# GK_Roland_Breakout.net
KiCad netlist of a schematic drawn in EAGLE
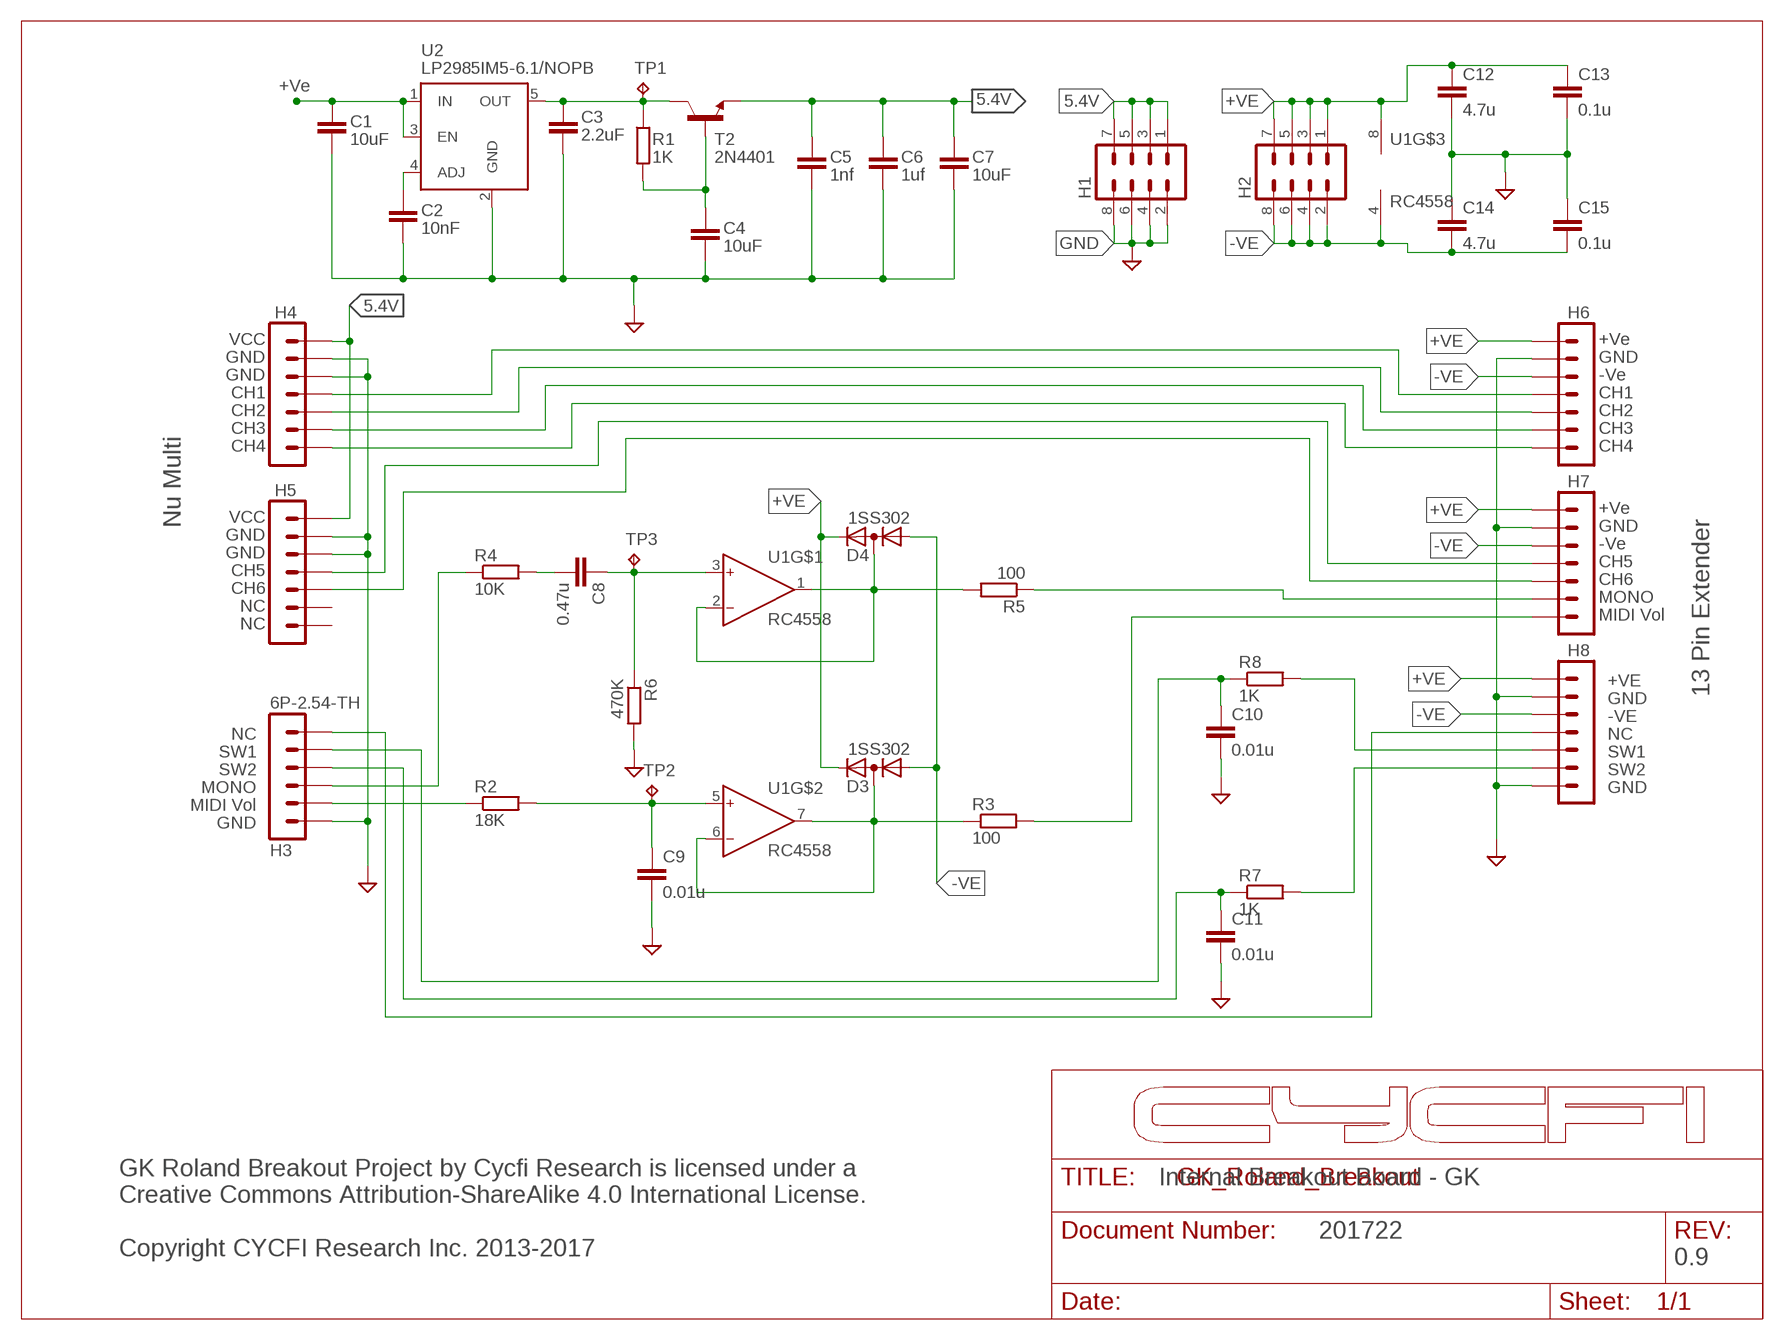
[diagram p0: schematic, sheet 1]

(export (version "E")
  (design (tool "Eeschema 10.0.6"))
  (components
    (comp (ref "C1")
      (value "10uF")
      (footprint "eagle-import:C0805")
      (libsource (lib "eagle-import") (part "C-EUC0805"))
    )
    (comp (ref "C2")
      (value "10nF")
      (footprint "eagle-import:C0805")
      (libsource (lib "eagle-import") (part "C-EUC0805"))
    )
    (comp (ref "C3")
      (value "2.2uF")
      (footprint "eagle-import:C0805")
      (libsource (lib "eagle-import") (part "C-EUC0805"))
    )
    (comp (ref "C4")
      (value "10uF")
      (footprint "eagle-import:C0805")
      (libsource (lib "eagle-import") (part "C-EUC0805"))
    )
    (comp (ref "C5")
      (value "1nf")
      (footprint "eagle-import:C0603")
      (libsource (lib "eagle-import") (part "C-EUC0603"))
    )
    (comp (ref "C6")
      (value "1uf")
      (footprint "eagle-import:C0603")
      (libsource (lib "eagle-import") (part "C-EUC0603"))
    )
    (comp (ref "C7")
      (value "10uF")
      (footprint "eagle-import:C0805")
      (libsource (lib "eagle-import") (part "C-EUC0805"))
    )
    (comp (ref "C8")
      (value "0.47u")
      (footprint "eagle-import:C0805")
      (libsource (lib "eagle-import") (part "C-EUC0805"))
    )
    (comp (ref "C9")
      (value "0.01u")
      (footprint "eagle-import:C0805")
      (libsource (lib "eagle-import") (part "C-EUC0805"))
    )
    (comp (ref "C10")
      (value "0.01u")
      (footprint "eagle-import:C0805")
      (libsource (lib "eagle-import") (part "C-EUC0805"))
    )
    (comp (ref "C11")
      (value "0.01u")
      (footprint "eagle-import:C0805")
      (libsource (lib "eagle-import") (part "C-EUC0805"))
    )
    (comp (ref "C12")
      (value "4.7u")
      (footprint "eagle-import:C0805")
      (libsource (lib "eagle-import") (part "C-EUC0805"))
    )
    (comp (ref "C13")
      (value "0.1u")
      (footprint "eagle-import:C0805")
      (libsource (lib "eagle-import") (part "C-EUC0805"))
    )
    (comp (ref "C14")
      (value "4.7u")
      (footprint "eagle-import:C0805")
      (libsource (lib "eagle-import") (part "C-EUC0805"))
    )
    (comp (ref "C15")
      (value "0.1u")
      (footprint "eagle-import:C0805")
      (libsource (lib "eagle-import") (part "C-EUC0805"))
    )
    (comp (ref "D3")
      (value "1SS302")
      (footprint "eagle-import:SC70-3")
      (libsource (lib "eagle-import") (part "1SS302"))
    )
    (comp (ref "D4")
      (value "1SS302")
      (footprint "eagle-import:SC70-3")
      (libsource (lib "eagle-import") (part "1SS302"))
    )
    (comp (ref "H1")
      (value "MA04-2")
      (footprint "eagle-import:MA04-2")
      (libsource (lib "eagle-import") (part "MA04-2"))
    )
    (comp (ref "H2")
      (value "MA04-2")
      (footprint "eagle-import:MA04-2")
      (libsource (lib "eagle-import") (part "MA04-2"))
    )
    (comp (ref "H3")
      (value "6P-2.54-TH")
      (footprint "eagle-import:6P-2.54-TH")
      (libsource (lib "eagle-import") (part "6P-2.54-TH"))
    )
    (comp (ref "H4")
      (value "7P_ZIF_59453-071110EDHLF")
      (footprint "eagle-import:7P_ZIF_59453-071110EDHLF")
      (libsource (lib "eagle-import") (part "7P_ZIF_59453-071110EDHLF"))
    )
    (comp (ref "H5")
      (value "7P_ZIF_59453-071110EDHLF")
      (footprint "eagle-import:7P_ZIF_59453-071110EDHLF")
      (libsource (lib "eagle-import") (part "7P_ZIF_59453-071110EDHLF"))
    )
    (comp (ref "H6")
      (value "7P_ZIF_59453-071110EDHLF")
      (footprint "eagle-import:7P_ZIF_59453-071110EDHLF")
      (libsource (lib "eagle-import") (part "7P_ZIF_59453-071110EDHLF"))
    )
    (comp (ref "H7")
      (value "7P_ZIF_59453-071110EDHLF")
      (footprint "eagle-import:7P_ZIF_59453-071110EDHLF")
      (libsource (lib "eagle-import") (part "7P_ZIF_59453-071110EDHLF"))
    )
    (comp (ref "H8")
      (value "7P_ZIF_59453-071110EDHLF")
      (footprint "eagle-import:7P_ZIF_59453-071110EDHLF")
      (libsource (lib "eagle-import") (part "7P_ZIF_59453-071110EDHLF"))
    )
    (comp (ref "R1")
      (value "1K")
      (footprint "eagle-import:R0402")
      (libsource (lib "eagle-import") (part "R-EU_R0402"))
    )
    (comp (ref "R2")
      (value "18K")
      (footprint "eagle-import:R0402")
      (libsource (lib "eagle-import") (part "R-EU_R0402"))
    )
    (comp (ref "R3")
      (value "100")
      (footprint "eagle-import:R0402")
      (libsource (lib "eagle-import") (part "R-EU_R0402"))
    )
    (comp (ref "R4")
      (value "10K")
      (footprint "eagle-import:R0402")
      (libsource (lib "eagle-import") (part "R-EU_R0402"))
    )
    (comp (ref "R5")
      (value "100")
      (footprint "eagle-import:R0402")
      (libsource (lib "eagle-import") (part "R-EU_R0402"))
    )
    (comp (ref "R6")
      (value "470K")
      (footprint "eagle-import:R0402")
      (libsource (lib "eagle-import") (part "R-EU_R0402"))
    )
    (comp (ref "R7")
      (value "1K")
      (footprint "eagle-import:R0402")
      (libsource (lib "eagle-import") (part "R-EU_R0402"))
    )
    (comp (ref "R8")
      (value "1K")
      (footprint "eagle-import:R0402")
      (libsource (lib "eagle-import") (part "R-EU_R0402"))
    )
    (comp (ref "T2")
      (value "2N4401")
      (footprint "eagle-import:SOT23-3")
      (libsource (lib "eagle-import") (part "TRAN-MMBT2222A"))
    )
    (comp (ref "TP1")
      (value "TPB1,27")
      (footprint "eagle-import:B1,27")
      (libsource (lib "eagle-import") (part "TPB1,27"))
    )
    (comp (ref "TP2")
      (value "TPB1,27")
      (footprint "eagle-import:B1,27")
      (libsource (lib "eagle-import") (part "TPB1,27"))
    )
    (comp (ref "TP3")
      (value "TPB1,27")
      (footprint "eagle-import:B1,27")
      (libsource (lib "eagle-import") (part "TPB1,27"))
    )
    (comp (ref "U1")
      (value "RC4558")
      (footprint "eagle-import:SOIC-8")
      (libsource (lib "eagle-import") (part "RC4558"))
    )
    (comp (ref "U2")
      (value "MIC5205-5V")
      (footprint "eagle-import:SOT23-5")
      (fields (field (name "MF") "ALTERA CORPORATION") (field (name "MPN") "MIC5219BM5 TR"))
      (libsource (lib "eagle-import") (part "MIC5219BM5"))
    )
  )
  (nets
    (net (code "1") (name "+VE") (class "Default")
      (node (ref "C1") (pin "1") (pinfunction "1_1") (pintype "passive"))
      (node (ref "C12") (pin "1") (pinfunction "1_1") (pintype "passive"))
      (node (ref "C13") (pin "1") (pinfunction "1_1") (pintype "passive"))
      (node (ref "D3") (pin "2") (pinfunction "K_2") (pintype "passive"))
      (node (ref "D4") (pin "2") (pinfunction "K_2") (pintype "passive"))
      (node (ref "H2") (pin "1") (pinfunction "1_1") (pintype "passive"))
      (node (ref "H2") (pin "3") (pinfunction "3_3") (pintype "passive"))
      (node (ref "H2") (pin "5") (pinfunction "5_5") (pintype "passive"))
      (node (ref "H2") (pin "7") (pinfunction "7_7") (pintype "passive"))
      (node (ref "H6") (pin "P$1") (pinfunction "1_P$1") (pintype "passive"))
      (node (ref "H7") (pin "P$1") (pinfunction "1_P$1") (pintype "passive"))
      (node (ref "H8") (pin "P$1") (pinfunction "1_P$1") (pintype "passive"))
      (node (ref "U1") (pin "8") (pinfunction "V+_8") (pintype "power_in"))
      (node (ref "U2") (pin "1") (pinfunction "IN_1") (pintype "input"))
      (node (ref "U2") (pin "3") (pinfunction "EN_3") (pintype "input"))
    )
    (net (code "2") (name "-VE") (class "Default")
      (node (ref "C14") (pin "2") (pinfunction "2_2") (pintype "passive"))
      (node (ref "C15") (pin "2") (pinfunction "2_2") (pintype "passive"))
      (node (ref "D3") (pin "1") (pinfunction "A_1") (pintype "passive"))
      (node (ref "D4") (pin "1") (pinfunction "A_1") (pintype "passive"))
      (node (ref "H2") (pin "2") (pinfunction "2_2") (pintype "passive"))
      (node (ref "H2") (pin "4") (pinfunction "4_4") (pintype "passive"))
      (node (ref "H2") (pin "6") (pinfunction "6_6") (pintype "passive"))
      (node (ref "H2") (pin "8") (pinfunction "8_8") (pintype "passive"))
      (node (ref "H6") (pin "P$3") (pinfunction "3_P$3") (pintype "passive"))
      (node (ref "H7") (pin "P$3") (pinfunction "3_P$3") (pintype "passive"))
      (node (ref "H8") (pin "P$3") (pinfunction "3_P$3") (pintype "passive"))
      (node (ref "U1") (pin "4") (pinfunction "V-_4") (pintype "power_in"))
    )
    (net (code "3") (name "5.4V") (class "Default")
      (node (ref "C5") (pin "1") (pinfunction "1_1") (pintype "passive"))
      (node (ref "C6") (pin "1") (pinfunction "1_1") (pintype "passive"))
      (node (ref "C7") (pin "1") (pinfunction "1_1") (pintype "passive"))
      (node (ref "H1") (pin "1") (pinfunction "1_1") (pintype "passive"))
      (node (ref "H1") (pin "3") (pinfunction "3_3") (pintype "passive"))
      (node (ref "H1") (pin "5") (pinfunction "5_5") (pintype "passive"))
      (node (ref "H1") (pin "7") (pinfunction "7_7") (pintype "passive"))
      (node (ref "H4") (pin "P$1") (pinfunction "1_P$1") (pintype "passive"))
      (node (ref "H5") (pin "P$1") (pinfunction "1_P$1") (pintype "passive"))
      (node (ref "T2") (pin "2") (pinfunction "E_2") (pintype "passive"))
    )
    (net (code "4") (name "GND") (class "Default")
      (node (ref "C1") (pin "2") (pinfunction "2_2") (pintype "passive"))
      (node (ref "C10") (pin "2") (pinfunction "2_2") (pintype "passive"))
      (node (ref "C11") (pin "2") (pinfunction "2_2") (pintype "passive"))
      (node (ref "C12") (pin "2") (pinfunction "2_2") (pintype "passive"))
      (node (ref "C13") (pin "2") (pinfunction "2_2") (pintype "passive"))
      (node (ref "C14") (pin "1") (pinfunction "1_1") (pintype "passive"))
      (node (ref "C15") (pin "1") (pinfunction "1_1") (pintype "passive"))
      (node (ref "C2") (pin "2") (pinfunction "2_2") (pintype "passive"))
      (node (ref "C3") (pin "2") (pinfunction "2_2") (pintype "passive"))
      (node (ref "C4") (pin "2") (pinfunction "2_2") (pintype "passive"))
      (node (ref "C5") (pin "2") (pinfunction "2_2") (pintype "passive"))
      (node (ref "C6") (pin "2") (pinfunction "2_2") (pintype "passive"))
      (node (ref "C7") (pin "2") (pinfunction "2_2") (pintype "passive"))
      (node (ref "C9") (pin "2") (pinfunction "2_2") (pintype "passive"))
      (node (ref "H1") (pin "2") (pinfunction "2_2") (pintype "passive"))
      (node (ref "H1") (pin "4") (pinfunction "4_4") (pintype "passive"))
      (node (ref "H1") (pin "6") (pinfunction "6_6") (pintype "passive"))
      (node (ref "H1") (pin "8") (pinfunction "8_8") (pintype "passive"))
      (node (ref "H3") (pin "6") (pinfunction "6_6") (pintype "passive"))
      (node (ref "H4") (pin "P$2") (pinfunction "2_P$2") (pintype "passive"))
      (node (ref "H4") (pin "P$3") (pinfunction "3_P$3") (pintype "passive"))
      (node (ref "H5") (pin "P$2") (pinfunction "2_P$2") (pintype "passive"))
      (node (ref "H5") (pin "P$3") (pinfunction "3_P$3") (pintype "passive"))
      (node (ref "H6") (pin "P$2") (pinfunction "2_P$2") (pintype "passive"))
      (node (ref "H7") (pin "P$2") (pinfunction "2_P$2") (pintype "passive"))
      (node (ref "H8") (pin "P$2") (pinfunction "2_P$2") (pintype "passive"))
      (node (ref "H8") (pin "P$7") (pinfunction "7_P$7") (pintype "passive"))
      (node (ref "R6") (pin "2") (pinfunction "2_2") (pintype "passive"))
      (node (ref "U2") (pin "2") (pinfunction "GND_2") (pintype "power_in"))
    )
    (net (code "5") (name "Net-(C8-Pad2)") (class "Default")
      (node (ref "C8") (pin "2") (pinfunction "2_2") (pintype "passive"))
      (node (ref "R4") (pin "2") (pinfunction "2_2") (pintype "passive"))
    )
    (net (code "6") (name "Net-(C10-Pad1)") (class "Default")
      (node (ref "C10") (pin "1") (pinfunction "1_1") (pintype "passive"))
      (node (ref "H3") (pin "2") (pinfunction "2_2") (pintype "passive"))
      (node (ref "R8") (pin "1") (pinfunction "1_1") (pintype "passive"))
    )
    (net (code "7") (name "Net-(C11-Pad1)") (class "Default")
      (node (ref "C11") (pin "1") (pinfunction "1_1") (pintype "passive"))
      (node (ref "H3") (pin "3") (pinfunction "3_3") (pintype "passive"))
      (node (ref "R7") (pin "1") (pinfunction "1_1") (pintype "passive"))
    )
    (net (code "8") (name "Net-(D3-AK)") (class "Default")
      (node (ref "D3") (pin "3") (pinfunction "AK_3") (pintype "passive"))
      (node (ref "R3") (pin "1") (pinfunction "1_1") (pintype "passive"))
      (node (ref "U1") (pin "6") (pinfunction "IN-_6") (pintype "input"))
      (node (ref "U1") (pin "7") (pinfunction "OUT_7") (pintype "output"))
    )
    (net (code "9") (name "Net-(D4-AK)") (class "Default")
      (node (ref "D4") (pin "3") (pinfunction "AK_3") (pintype "passive"))
      (node (ref "R5") (pin "2") (pinfunction "2_2") (pintype "passive"))
      (node (ref "U1") (pin "1") (pinfunction "OUT_1") (pintype "output"))
      (node (ref "U1") (pin "2") (pinfunction "IN-_2") (pintype "input"))
    )
    (net (code "10") (name "Net-(H3-Pad4)") (class "Default")
      (node (ref "H3") (pin "4") (pinfunction "4_4") (pintype "passive"))
      (node (ref "R4") (pin "1") (pinfunction "1_1") (pintype "passive"))
    )
    (net (code "11") (name "Net-(H3-Pad5)") (class "Default")
      (node (ref "H3") (pin "5") (pinfunction "5_5") (pintype "passive"))
      (node (ref "R2") (pin "1") (pinfunction "1_1") (pintype "passive"))
    )
    (net (code "12") (name "Net-(H4-4)") (class "Default")
      (node (ref "H4") (pin "P$4") (pinfunction "4_P$4") (pintype "passive"))
      (node (ref "H6") (pin "P$4") (pinfunction "4_P$4") (pintype "passive"))
    )
    (net (code "13") (name "Net-(H4-5)") (class "Default")
      (node (ref "H4") (pin "P$5") (pinfunction "5_P$5") (pintype "passive"))
      (node (ref "H6") (pin "P$5") (pinfunction "5_P$5") (pintype "passive"))
    )
    (net (code "14") (name "Net-(H4-6)") (class "Default")
      (node (ref "H4") (pin "P$6") (pinfunction "6_P$6") (pintype "passive"))
      (node (ref "H6") (pin "P$6") (pinfunction "6_P$6") (pintype "passive"))
    )
    (net (code "15") (name "Net-(H4-7)") (class "Default")
      (node (ref "H4") (pin "P$7") (pinfunction "7_P$7") (pintype "passive"))
      (node (ref "H6") (pin "P$7") (pinfunction "7_P$7") (pintype "passive"))
    )
    (net (code "16") (name "Net-(H5-4)") (class "Default")
      (node (ref "H5") (pin "P$4") (pinfunction "4_P$4") (pintype "passive"))
      (node (ref "H7") (pin "P$4") (pinfunction "4_P$4") (pintype "passive"))
    )
    (net (code "17") (name "Net-(H5-5)") (class "Default")
      (node (ref "H5") (pin "P$5") (pinfunction "5_P$5") (pintype "passive"))
      (node (ref "H7") (pin "P$5") (pinfunction "5_P$5") (pintype "passive"))
    )
    (net (code "18") (name "Net-(H7-6)") (class "Default")
      (node (ref "H7") (pin "P$6") (pinfunction "6_P$6") (pintype "passive"))
      (node (ref "R5") (pin "1") (pinfunction "1_1") (pintype "passive"))
    )
    (net (code "19") (name "Net-(H7-7)") (class "Default")
      (node (ref "H7") (pin "P$7") (pinfunction "7_P$7") (pintype "passive"))
      (node (ref "R3") (pin "2") (pinfunction "2_2") (pintype "passive"))
    )
    (net (code "20") (name "Net-(H8-4)") (class "Default")
      (node (ref "H3") (pin "1") (pinfunction "1_1") (pintype "passive"))
      (node (ref "H8") (pin "P$4") (pinfunction "4_P$4") (pintype "passive"))
    )
    (net (code "21") (name "Net-(H8-5)") (class "Default")
      (node (ref "H8") (pin "P$5") (pinfunction "5_P$5") (pintype "passive"))
      (node (ref "R8") (pin "2") (pinfunction "2_2") (pintype "passive"))
    )
    (net (code "22") (name "Net-(H8-6)") (class "Default")
      (node (ref "H8") (pin "P$6") (pinfunction "6_P$6") (pintype "passive"))
      (node (ref "R7") (pin "2") (pinfunction "2_2") (pintype "passive"))
    )
    (net (code "23") (name "Net-(T2-B)") (class "Default")
      (node (ref "C4") (pin "1") (pinfunction "1_1") (pintype "passive"))
      (node (ref "R1") (pin "2") (pinfunction "2_2") (pintype "passive"))
      (node (ref "T2") (pin "1") (pinfunction "B_1") (pintype "passive"))
    )
    (net (code "24") (name "Net-(T2-C)") (class "Default")
      (node (ref "C3") (pin "1") (pinfunction "1_1") (pintype "passive"))
      (node (ref "R1") (pin "1") (pinfunction "1_1") (pintype "passive"))
      (node (ref "T2") (pin "3") (pinfunction "C_3") (pintype "passive"))
      (node (ref "TP1") (pin "TP") (pinfunction "TP_TP") (pintype "input"))
      (node (ref "U2") (pin "5") (pinfunction "OUT_5") (pintype "output"))
    )
    (net (code "25") (name "Net-(U1A-IN+)") (class "Default")
      (node (ref "C8") (pin "1") (pinfunction "1_1") (pintype "passive"))
      (node (ref "R6") (pin "1") (pinfunction "1_1") (pintype "passive"))
      (node (ref "TP3") (pin "TP") (pinfunction "TP_TP") (pintype "input"))
      (node (ref "U1") (pin "3") (pinfunction "IN+_3") (pintype "input"))
    )
    (net (code "26") (name "Net-(U1B-IN+)") (class "Default")
      (node (ref "C9") (pin "1") (pinfunction "1_1") (pintype "passive"))
      (node (ref "R2") (pin "2") (pinfunction "2_2") (pintype "passive"))
      (node (ref "TP2") (pin "TP") (pinfunction "TP_TP") (pintype "input"))
      (node (ref "U1") (pin "5") (pinfunction "IN+_5") (pintype "input"))
    )
    (net (code "27") (name "Net-(U2-ADJ)") (class "Default")
      (node (ref "C2") (pin "1") (pinfunction "1_1") (pintype "passive"))
      (node (ref "U2") (pin "4") (pinfunction "ADJ_4") (pintype "passive"))
    )
    (net (code "28") (name "unconnected-(H5-6-PadP$6)") (class "Default")
      (node (ref "H5") (pin "P$6") (pinfunction "6_P$6") (pintype "passive"))
    )
    (net (code "29") (name "unconnected-(H5-7-PadP$7)") (class "Default")
      (node (ref "H5") (pin "P$7") (pinfunction "7_P$7") (pintype "passive"))
    )
  )
)
